# Schematic.net
KiCad netlist of a schematic drawn in EAGLE
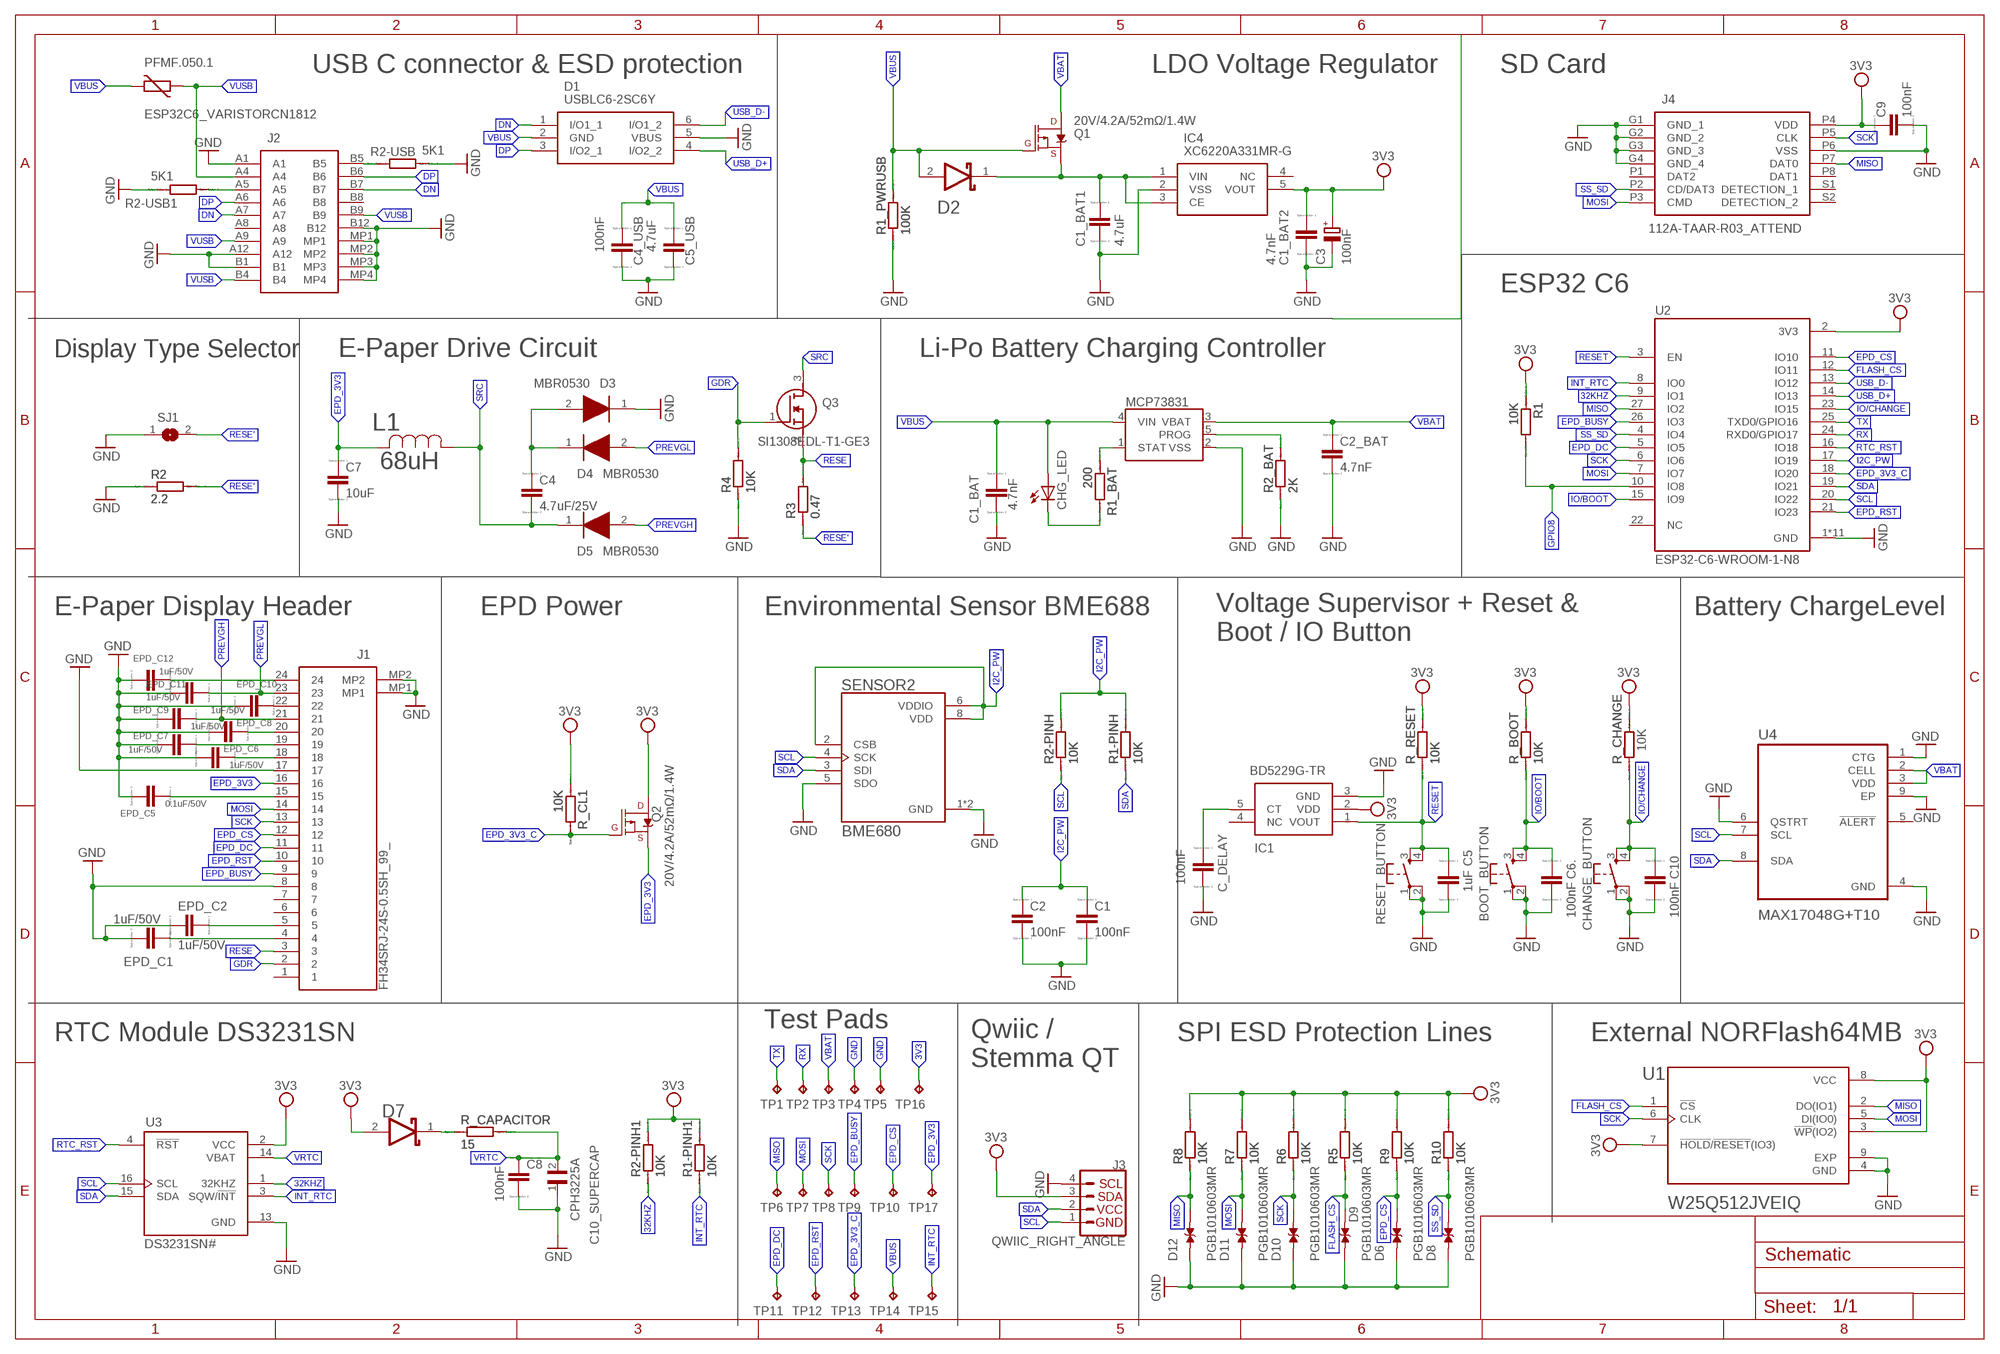
[diagram p0: schematic, sheet 1]

(export (version "E")
  (design (tool "Eeschema 10.0.6"))
  (components
    (comp (ref "BOOT_BUTTON")
      (value "BUTTON_CUSYOMV1")
      (footprint "eagle-import:MYBUTTON")
      (libsource (lib "eagle-import") (part "BUTTON_CUSYOMV1"))
    )
    (comp (ref "C1")
      (value "100nF")
      (footprint "eagle-import:ESP32_WROVER_EAGLE-LTSPICE_C0402")
      (libsource (lib "eagle-import") (part "EAGLE-LTSPICE_CC0402"))
    )
    (comp (ref "C1_BAT")
      (value "4.7nF")
      (footprint "eagle-import:ESP32_WROVER_EAGLE-LTSPICE_C0402")
      (libsource (lib "eagle-import") (part "EAGLE-LTSPICE_CC0402"))
    )
    (comp (ref "C1_BAT1")
      (value "4.7uF")
      (footprint "eagle-import:ESP32_WROVER_EAGLE-LTSPICE_C0402")
      (libsource (lib "eagle-import") (part "EAGLE-LTSPICE_CC0402"))
    )
    (comp (ref "C1_BAT2")
      (value "4.7nF")
      (footprint "eagle-import:ESP32_WROVER_EAGLE-LTSPICE_C0402")
      (libsource (lib "eagle-import") (part "EAGLE-LTSPICE_CC0402"))
    )
    (comp (ref "C2")
      (value "100nF")
      (footprint "eagle-import:ESP32_WROVER_EAGLE-LTSPICE_C0402")
      (libsource (lib "eagle-import") (part "EAGLE-LTSPICE_CC0402"))
    )
    (comp (ref "C2_BAT")
      (value "4.7nF")
      (footprint "eagle-import:ESP32_WROVER_EAGLE-LTSPICE_C0402")
      (libsource (lib "eagle-import") (part "EAGLE-LTSPICE_CC0402"))
    )
    (comp (ref "C3")
      (value "100nF")
      (footprint "eagle-import:RCL_CT3528")
      (libsource (lib "eagle-import") (part "RCL_CPOL-EUCT3528"))
    )
    (comp (ref "C4")
      (value "4.7uF/25V")
      (footprint "eagle-import:ESP32_WROVER_EAGLE-LTSPICE_C0402")
      (libsource (lib "eagle-import") (part "EAGLE-LTSPICE_CC0402"))
    )
    (comp (ref "C4_USB")
      (value "100nF")
      (footprint "eagle-import:ESP32_WROVER_EAGLE-LTSPICE_C0402")
      (libsource (lib "eagle-import") (part "EAGLE-LTSPICE_CC0402"))
    )
    (comp (ref "C5")
      (value "1uF")
      (footprint "eagle-import:ESP32_WROVER_EAGLE-LTSPICE_C0402")
      (libsource (lib "eagle-import") (part "EAGLE-LTSPICE_CC0402"))
    )
    (comp (ref "C5_USB")
      (value "4.7uF")
      (footprint "eagle-import:ESP32_WROVER_EAGLE-LTSPICE_C0402")
      (libsource (lib "eagle-import") (part "EAGLE-LTSPICE_CC0402"))
    )
    (comp (ref "C6.")
      (value "100nF")
      (footprint "eagle-import:ESP32_WROVER_EAGLE-LTSPICE_C0402")
      (libsource (lib "eagle-import") (part "EAGLE-LTSPICE_CC0402"))
    )
    (comp (ref "C7")
      (value "10uF")
      (footprint "eagle-import:ESP32_WROVER_EAGLE-LTSPICE_C0402")
      (libsource (lib "eagle-import") (part "EAGLE-LTSPICE_CC0402"))
    )
    (comp (ref "C8")
      (value "100nF")
      (footprint "eagle-import:ESP32_WROVER_EAGLE-LTSPICE_C0402")
      (libsource (lib "eagle-import") (part "EAGLE-LTSPICE_CC0402"))
    )
    (comp (ref "C9")
      (value "100nF")
      (footprint "eagle-import:ESP32_WROVER_EAGLE-LTSPICE_C0402")
      (libsource (lib "eagle-import") (part "EAGLE-LTSPICE_CC0402"))
    )
    (comp (ref "C10")
      (value "100nF")
      (footprint "eagle-import:ESP32_WROVER_EAGLE-LTSPICE_C0402")
      (libsource (lib "eagle-import") (part "EAGLE-LTSPICE_CC0402"))
    )
    (comp (ref "C10_SUPERCAP")
      (value "CPH3225A")
      (footprint "eagle-import:CAPCP3225X100N")
      (fields (field (name "MF") "Seiko Instruments"))
      (libsource (lib "eagle-import") (part "CPH3225A"))
    )
    (comp (ref "CHANGE_BUTTON")
      (value "BUTTON_CUSYOMV1")
      (footprint "eagle-import:MYBUTTON")
      (libsource (lib "eagle-import") (part "BUTTON_CUSYOMV1"))
    )
    (comp (ref "CHG_LED")
      (value "ADAFRUIT_LEDCHIP-LED0603")
      (footprint "eagle-import:ADAFRUIT_CHIP-LED0603")
      (libsource (lib "eagle-import") (part "ADAFRUIT_LEDCHIP-LED0603"))
    )
    (comp (ref "C_DELAY")
      (value "100nF")
      (footprint "eagle-import:ESP32_WROVER_EAGLE-LTSPICE_C0402")
      (libsource (lib "eagle-import") (part "EAGLE-LTSPICE_CC0402"))
    )
    (comp (ref "D1")
      (value "USBLC6-2SC6Y")
      (footprint "eagle-import:SOT95P280X145-6N")
      (fields (field (name "MF") "STMicroelectronics"))
      (libsource (lib "eagle-import") (part "USBLC6-2SC6Y"))
    )
    (comp (ref "D2")
      (value "ESP32_WROVER_AVX---SD0805S020S1R0_AVX_SD0805S020S1R0_0_0AVX_SD0805S020S1R0_0_0")
      (footprint "eagle-import:ESP32_WROVER_AVX---SD0805S020S1R0_AVX_SD0805S020S1R0_0")
      (fields
        (field (name "DIGIKEY_PART_NUMBER") "478-7800-1-ND")
        (field (name "MF") "AVX")
        (field (name "MOUSER_PART_NUMBER") "581-SD0805S020S1R0")
      )
      (libsource (lib "eagle-import") (part "ESP32_WROVER_AVX---SD0805S020S1R0_AVX_SD0805S020S1R0_0_0AVX_SD0805S020S1R0_0_0"))
    )
    (comp (ref "D3")
      (value "MBR0530")
      (footprint "eagle-import:SOD3716X135N")
      (fields (field (name "MF") "ON Semiconductor"))
      (libsource (lib "eagle-import") (part "MBR0530"))
    )
    (comp (ref "D4")
      (value "MBR0530")
      (footprint "eagle-import:SOD3716X135N")
      (fields (field (name "MF") "ON Semiconductor"))
      (libsource (lib "eagle-import") (part "MBR0530"))
    )
    (comp (ref "D5")
      (value "MBR0530")
      (footprint "eagle-import:SOD3716X135N")
      (fields (field (name "MF") "ON Semiconductor"))
      (libsource (lib "eagle-import") (part "MBR0530"))
    )
    (comp (ref "D6")
      (value "PGB1010603MR")
      (footprint "eagle-import:DIOC1608X36N")
      (fields (field (name "MF") "Littelfuse Inc."))
      (libsource (lib "eagle-import") (part "PGB1010603MR"))
    )
    (comp (ref "D7")
      (value "SD0805S020S1R0")
      (footprint "eagle-import:ESP32_WROVER_AVX---SD0805S020S1R0_AVX_SD0805S020S1R0_0")
      (fields
        (field (name "DIGIKEY_PART_NUMBER") "478-7800-1-ND")
        (field (name "MF") "AVX")
        (field (name "MOUSER_PART_NUMBER") "581-SD0805S020S1R0")
      )
      (libsource (lib "eagle-import") (part "ESP32_WROVER_AVX---SD0805S020S1R0_AVX_SD0805S020S1R0_0_0AVX_SD0805S020S1R0_0_0"))
    )
    (comp (ref "D8")
      (value "PGB1010603MR")
      (footprint "eagle-import:DIOC1608X36N")
      (fields (field (name "MF") "Littelfuse Inc."))
      (libsource (lib "eagle-import") (part "PGB1010603MR"))
    )
    (comp (ref "D9")
      (value "PGB1010603MR")
      (footprint "eagle-import:DIOC1608X36N")
      (fields (field (name "MF") "Littelfuse Inc."))
      (libsource (lib "eagle-import") (part "PGB1010603MR"))
    )
    (comp (ref "D10")
      (value "PGB1010603MR")
      (footprint "eagle-import:DIOC1608X36N")
      (fields (field (name "MF") "Littelfuse Inc."))
      (libsource (lib "eagle-import") (part "PGB1010603MR"))
    )
    (comp (ref "D11")
      (value "PGB1010603MR")
      (footprint "eagle-import:DIOC1608X36N")
      (fields (field (name "MF") "Littelfuse Inc."))
      (libsource (lib "eagle-import") (part "PGB1010603MR"))
    )
    (comp (ref "D12")
      (value "PGB1010603MR")
      (footprint "eagle-import:DIOC1608X36N")
      (fields (field (name "MF") "Littelfuse Inc."))
      (libsource (lib "eagle-import") (part "PGB1010603MR"))
    )
    (comp (ref "EPD_C1")
      (value "1uF/50V")
      (footprint "eagle-import:ESP32_WROVER_EAGLE-LTSPICE_C0402")
      (libsource (lib "eagle-import") (part "EAGLE-LTSPICE_CC0402"))
    )
    (comp (ref "EPD_C2")
      (value "1uF/50V")
      (footprint "eagle-import:ESP32_WROVER_EAGLE-LTSPICE_C0402")
      (libsource (lib "eagle-import") (part "EAGLE-LTSPICE_CC0402"))
    )
    (comp (ref "EPD_C5")
      (value "0.1uF/50V")
      (footprint "eagle-import:ESP32_WROVER_EAGLE-LTSPICE_C0402")
      (libsource (lib "eagle-import") (part "EAGLE-LTSPICE_CC0402"))
    )
    (comp (ref "EPD_C6")
      (value "1uF/50V")
      (footprint "eagle-import:ESP32_WROVER_EAGLE-LTSPICE_C0402")
      (libsource (lib "eagle-import") (part "EAGLE-LTSPICE_CC0402"))
    )
    (comp (ref "EPD_C7")
      (value "1uF/50V")
      (footprint "eagle-import:ESP32_WROVER_EAGLE-LTSPICE_C0402")
      (libsource (lib "eagle-import") (part "EAGLE-LTSPICE_CC0402"))
    )
    (comp (ref "EPD_C8")
      (value "1uF/50V")
      (footprint "eagle-import:ESP32_WROVER_EAGLE-LTSPICE_C0402")
      (libsource (lib "eagle-import") (part "EAGLE-LTSPICE_CC0402"))
    )
    (comp (ref "EPD_C9")
      (value "EAGLE-LTSPICE_CC0402")
      (footprint "eagle-import:ESP32_WROVER_EAGLE-LTSPICE_C0402")
      (libsource (lib "eagle-import") (part "EAGLE-LTSPICE_CC0402"))
    )
    (comp (ref "EPD_C10")
      (value "1uF/50V")
      (footprint "eagle-import:ESP32_WROVER_EAGLE-LTSPICE_C0402")
      (libsource (lib "eagle-import") (part "EAGLE-LTSPICE_CC0402"))
    )
    (comp (ref "EPD_C11")
      (value "1uF/50V")
      (footprint "eagle-import:ESP32_WROVER_EAGLE-LTSPICE_C0402")
      (libsource (lib "eagle-import") (part "EAGLE-LTSPICE_CC0402"))
    )
    (comp (ref "EPD_C12")
      (value "1uF/50V")
      (footprint "eagle-import:ESP32_WROVER_EAGLE-LTSPICE_C0402")
      (libsource (lib "eagle-import") (part "EAGLE-LTSPICE_CC0402"))
    )
    (comp (ref "IC1")
      (value "BD5229G-TR")
      (footprint "eagle-import:SOT95P280X125-5N")
      (fields (field (name "MOUSER_PART_NUMBER") "755-BD5229G-TR"))
      (libsource (lib "eagle-import") (part "BD5229G-TR"))
    )
    (comp (ref "IC4")
      (value "XC6220A331MR-G")
      (footprint "eagle-import:SOT95P280X120-5N")
      (fields (field (name "MOUSER_PART_NUMBER") "865-XC6220A331MR-G"))
      (libsource (lib "eagle-import") (part "XC6220A331MR-G"))
    )
    (comp (ref "J1")
      (value "FH34SRJ-24S-0.5SH_99_")
      (footprint "eagle-import:FH34SRJ24S05SH99")
      (fields
        (field (name "MANUFACTURER_PART_NUMBER") "FH34SRJ-24S-0.5SH(99)")
        (field (name "MOUSER_PART_NUMBER") "798-FH34SRJ24S05SH99")
      )
      (libsource (lib "eagle-import") (part "FH34SRJ-24S-0.5SH_99_"))
    )
    (comp (ref "J2")
      (value "SAMACSYS_PARTS_USB4110-GF-A")
      (footprint "eagle-import:SAMACSYS_PARTS_USB4110GFA")
      (fields
        (field (name "MANUFACTURER_PART_NUMBER") "USB4110-GF-A")
        (field (name "MOUSER_PART_NUMBER") "640-USB4110-GF-A")
      )
      (libsource (lib "eagle-import") (part "SAMACSYS_PARTS_USB4110-GF-A"))
    )
    (comp (ref "J3")
      (value "QWIIC_RIGHT_ANGLE")
      (footprint "eagle-import:JST04_1MM_RA")
      (libsource (lib "eagle-import") (part "QWIIC_CONNECTORJS-1MM"))
    )
    (comp (ref "J4")
      (value "112A-TAAR-R03_ATTEND")
      (footprint "eagle-import:112ATAARR03ATTEND")
      (fields (field (name "MANUFACTURER_PART_NUMBER") "112A-TAAR-R03 ATTEND"))
      (libsource (lib "eagle-import") (part "112A-TAAR-R03_ATTEND"))
    )
    (comp (ref "L1")
      (value "68uH")
      (footprint "eagle-import:IND_4828-WE-TPC_WRE")
      (fields
        (field (name "MANUFACTURER_PART_NUMBER") "744043680")
        (field (name "COPYRIGHT") "Copyright (C) 2024 Ultra Librarian. All rights reserved.")
      )
      (libsource (lib "eagle-import") (part "744043680IND_4828-WE-TPC_WRE"))
    )
    (comp (ref "MCP73831")
      (value "MCP73831")
      (footprint "eagle-import:ESP32_WROVER_SPARKFUN-IC-POWER_SOT23-5")
      (libsource (lib "eagle-import") (part "ESP32_WROVER_SPARKFUN-IC-POWER_MCP73831"))
    )
    (comp (ref "PFMF.050.1")
      (value "ESP32C6_VARISTORCN1812")
      (footprint "eagle-import:ESP32C6_VARISTOR_CT_CN1812")
      (libsource (lib "eagle-import") (part "ESP32C6_VARISTORCN1812"))
    )
    (comp (ref "Q1")
      (value "20V/4.2A/52mΩ/1.4W")
      (footprint "eagle-import:ESP32_WROVER_SPARKFUN-DISCRETESEMI_SOT23-3")
      (libsource (lib "eagle-import") (part "ESP32_WROVER_SPARKFUN-DISCRETESEMI_MOSFET_PCH-DMG2305UX-7"))
    )
    (comp (ref "Q2")
      (value "20V/4.2A/52mΩ/1.4W")
      (footprint "eagle-import:ESP32_WROVER_SPARKFUN-DISCRETESEMI_SOT23-3")
      (libsource (lib "eagle-import") (part "ESP32_WROVER_SPARKFUN-DISCRETESEMI_MOSFET_PCH-DMG2305UX-7"))
    )
    (comp (ref "Q3")
      (value "SI1308EDL-T1-GE3")
      (footprint "eagle-import:SOT65P210X110-3N")
      (fields (field (name "MF") "Vishay Siliconix"))
      (libsource (lib "eagle-import") (part "SI1308EDL-T1-GE3"))
    )
    (comp (ref "R1")
      (value "10K")
      (footprint "eagle-import:ESP32_WROVER_EAGLE-LTSPICE_R0402")
      (libsource (lib "eagle-import") (part "ESP32_WROVER_EAGLE-LTSPICE_RR0402"))
    )
    (comp (ref "R1-PINH")
      (value "10K")
      (footprint "eagle-import:ESP32_WROVER_EAGLE-LTSPICE_R0402")
      (libsource (lib "eagle-import") (part "ESP32_WROVER_EAGLE-LTSPICE_RR0402"))
    )
    (comp (ref "R1-PINH1")
      (value "10K")
      (footprint "eagle-import:ESP32_WROVER_EAGLE-LTSPICE_R0402")
      (libsource (lib "eagle-import") (part "ESP32_WROVER_EAGLE-LTSPICE_RR0402"))
    )
    (comp (ref "R1_BAT")
      (value "200")
      (footprint "eagle-import:ESP32_WROVER_EAGLE-LTSPICE_R0402")
      (libsource (lib "eagle-import") (part "ESP32_WROVER_EAGLE-LTSPICE_RR0402"))
    )
    (comp (ref "R1_PWRUSB")
      (value "100K")
      (footprint "eagle-import:ESP32_WROVER_EAGLE-LTSPICE_R0402")
      (libsource (lib "eagle-import") (part "ESP32_WROVER_EAGLE-LTSPICE_RR0402"))
    )
    (comp (ref "R2")
      (value "2.2")
      (footprint "eagle-import:ESP32_WROVER_EAGLE-LTSPICE_R0402")
      (libsource (lib "eagle-import") (part "ESP32_WROVER_EAGLE-LTSPICE_RR0402"))
    )
    (comp (ref "R2-PINH")
      (value "10K")
      (footprint "eagle-import:ESP32_WROVER_EAGLE-LTSPICE_R0402")
      (libsource (lib "eagle-import") (part "ESP32_WROVER_EAGLE-LTSPICE_RR0402"))
    )
    (comp (ref "R2-PINH1")
      (value "10K")
      (footprint "eagle-import:ESP32_WROVER_EAGLE-LTSPICE_R0402")
      (libsource (lib "eagle-import") (part "ESP32_WROVER_EAGLE-LTSPICE_RR0402"))
    )
    (comp (ref "R2-USB")
      (value "5K1")
      (footprint "eagle-import:ESP32_WROVER_EAGLE-LTSPICE_R0402")
      (libsource (lib "eagle-import") (part "ESP32_WROVER_EAGLE-LTSPICE_RR0402"))
    )
    (comp (ref "R2-USB1")
      (value "5K1")
      (footprint "eagle-import:ESP32_WROVER_EAGLE-LTSPICE_R0402")
      (libsource (lib "eagle-import") (part "ESP32_WROVER_EAGLE-LTSPICE_RR0402"))
    )
    (comp (ref "R2_BAT")
      (value "2K")
      (footprint "eagle-import:ESP32_WROVER_EAGLE-LTSPICE_R0402")
      (libsource (lib "eagle-import") (part "ESP32_WROVER_EAGLE-LTSPICE_RR0402"))
    )
    (comp (ref "R3")
      (value "0.47")
      (footprint "eagle-import:ESP32_WROVER_EAGLE-LTSPICE_R0402")
      (libsource (lib "eagle-import") (part "ESP32_WROVER_EAGLE-LTSPICE_RR0402"))
    )
    (comp (ref "R4")
      (value "10K")
      (footprint "eagle-import:ESP32_WROVER_EAGLE-LTSPICE_R0402")
      (libsource (lib "eagle-import") (part "ESP32_WROVER_EAGLE-LTSPICE_RR0402"))
    )
    (comp (ref "R5")
      (value "10K")
      (footprint "eagle-import:ESP32_WROVER_EAGLE-LTSPICE_R0402")
      (libsource (lib "eagle-import") (part "ESP32_WROVER_EAGLE-LTSPICE_RR0402"))
    )
    (comp (ref "R6")
      (value "10K")
      (footprint "eagle-import:ESP32_WROVER_EAGLE-LTSPICE_R0402")
      (libsource (lib "eagle-import") (part "ESP32_WROVER_EAGLE-LTSPICE_RR0402"))
    )
    (comp (ref "R7")
      (value "10K")
      (footprint "eagle-import:ESP32_WROVER_EAGLE-LTSPICE_R0402")
      (libsource (lib "eagle-import") (part "ESP32_WROVER_EAGLE-LTSPICE_RR0402"))
    )
    (comp (ref "R8")
      (value "10K")
      (footprint "eagle-import:ESP32_WROVER_EAGLE-LTSPICE_R0402")
      (libsource (lib "eagle-import") (part "ESP32_WROVER_EAGLE-LTSPICE_RR0402"))
    )
    (comp (ref "R9")
      (value "10K")
      (footprint "eagle-import:ESP32_WROVER_EAGLE-LTSPICE_R0402")
      (libsource (lib "eagle-import") (part "ESP32_WROVER_EAGLE-LTSPICE_RR0402"))
    )
    (comp (ref "R10")
      (value "10K")
      (footprint "eagle-import:ESP32_WROVER_EAGLE-LTSPICE_R0402")
      (libsource (lib "eagle-import") (part "ESP32_WROVER_EAGLE-LTSPICE_RR0402"))
    )
    (comp (ref "RESET_BUTTON")
      (value "BUTTON_CUSYOMV1")
      (footprint "eagle-import:MYBUTTON")
      (libsource (lib "eagle-import") (part "BUTTON_CUSYOMV1"))
    )
    (comp (ref "R_BOOT")
      (value "10K")
      (footprint "eagle-import:ESP32_WROVER_EAGLE-LTSPICE_R0402")
      (libsource (lib "eagle-import") (part "ESP32_WROVER_EAGLE-LTSPICE_RR0402"))
    )
    (comp (ref "R_CAPACITOR")
      (value "15")
      (footprint "eagle-import:ESP32_WROVER_EAGLE-LTSPICE_R0402")
      (libsource (lib "eagle-import") (part "ESP32_WROVER_EAGLE-LTSPICE_RR0402"))
    )
    (comp (ref "R_CHANGE")
      (value "10K")
      (footprint "eagle-import:ESP32_WROVER_EAGLE-LTSPICE_R0402")
      (libsource (lib "eagle-import") (part "ESP32_WROVER_EAGLE-LTSPICE_RR0402"))
    )
    (comp (ref "R_CL1")
      (value "10K")
      (footprint "eagle-import:ESP32_WROVER_EAGLE-LTSPICE_R0402")
      (libsource (lib "eagle-import") (part "ESP32_WROVER_EAGLE-LTSPICE_RR0402"))
    )
    (comp (ref "R_RESET")
      (value "10K")
      (footprint "eagle-import:ESP32_WROVER_EAGLE-LTSPICE_R0402")
      (libsource (lib "eagle-import") (part "ESP32_WROVER_EAGLE-LTSPICE_RR0402"))
    )
    (comp (ref "SENSOR2")
      (value "BME680")
      (footprint "eagle-import:ESP32_WROVER_BME680_PSON80P300X300X100-8N")
      (fields (field (name "MF") "Bosch Sensortec"))
      (libsource (lib "eagle-import") (part "ESP32_WROVER_BME680_BME680"))
    )
    (comp (ref "SJ1") (value "SJ") (footprint "eagle-import:SJ") (libsource (lib "eagle-import") (part "SJ")))
    (comp (ref "TP1")
      (value "TPTP20R")
      (footprint "eagle-import:TP20R")
      (libsource (lib "eagle-import") (part "TPTP20R"))
    )
    (comp (ref "TP2")
      (value "TPTP20R")
      (footprint "eagle-import:TP20R")
      (libsource (lib "eagle-import") (part "TPTP20R"))
    )
    (comp (ref "TP3")
      (value "TPTP20R")
      (footprint "eagle-import:TP20R")
      (libsource (lib "eagle-import") (part "TPTP20R"))
    )
    (comp (ref "TP4")
      (value "TPTP20R")
      (footprint "eagle-import:TP20R")
      (libsource (lib "eagle-import") (part "TPTP20R"))
    )
    (comp (ref "TP5")
      (value "TPTP20R")
      (footprint "eagle-import:TP20R")
      (libsource (lib "eagle-import") (part "TPTP20R"))
    )
    (comp (ref "TP6")
      (value "TPTP20R")
      (footprint "eagle-import:TP20R")
      (libsource (lib "eagle-import") (part "TPTP20R"))
    )
    (comp (ref "TP7")
      (value "TPTP20R")
      (footprint "eagle-import:TP20R")
      (libsource (lib "eagle-import") (part "TPTP20R"))
    )
    (comp (ref "TP8")
      (value "TPTP20R")
      (footprint "eagle-import:TP20R")
      (libsource (lib "eagle-import") (part "TPTP20R"))
    )
    (comp (ref "TP9")
      (value "TPTP20R")
      (footprint "eagle-import:TP20R")
      (libsource (lib "eagle-import") (part "TPTP20R"))
    )
    (comp (ref "TP10")
      (value "TPTP20R")
      (footprint "eagle-import:TP20R")
      (libsource (lib "eagle-import") (part "TPTP20R"))
    )
    (comp (ref "TP11")
      (value "TPTP20R")
      (footprint "eagle-import:TP20R")
      (libsource (lib "eagle-import") (part "TPTP20R"))
    )
    (comp (ref "TP12")
      (value "TPTP20R")
      (footprint "eagle-import:TP20R")
      (libsource (lib "eagle-import") (part "TPTP20R"))
    )
    (comp (ref "TP13")
      (value "TPTP20R")
      (footprint "eagle-import:TP20R")
      (libsource (lib "eagle-import") (part "TPTP20R"))
    )
    (comp (ref "TP14")
      (value "TPTP20R")
      (footprint "eagle-import:TP20R")
      (libsource (lib "eagle-import") (part "TPTP20R"))
    )
    (comp (ref "TP15")
      (value "TPTP20R")
      (footprint "eagle-import:TP20R")
      (libsource (lib "eagle-import") (part "TPTP20R"))
    )
    (comp (ref "TP16")
      (value "TPTP20R")
      (footprint "eagle-import:TP20R")
      (libsource (lib "eagle-import") (part "TPTP20R"))
    )
    (comp (ref "TP17")
      (value "TPTP20R")
      (footprint "eagle-import:TP20R")
      (libsource (lib "eagle-import") (part "TPTP20R"))
    )
    (comp (ref "U1")
      (value "W25Q512JVEIQ")
      (footprint "eagle-import:SON127P600X800X80-9N")
      (fields (field (name "MF") "Winbond Electronics"))
      (libsource (lib "eagle-import") (part "W25Q512JVEIQ"))
    )
    (comp (ref "U2")
      (value "ESP32-C6-WROOM-1-N8")
      (footprint "eagle-import:XCVR_ESP32-C6-WROOM-1-N8")
      (fields (field (name "MF") "Espressif Systems"))
      (libsource (lib "eagle-import") (part "ESP32-C6-WROOM-1-N8"))
    )
    (comp (ref "U3")
      (value "DS3231SN#")
      (footprint "eagle-import:SOIC127P1032X265-16N")
      (fields (field (name "MF") "Analog Devices"))
      (libsource (lib "eagle-import") (part "DS3231SN#"))
    )
    (comp (ref "U4")
      (value "MAX17048G+T10")
      (footprint "eagle-import:SON50P200X200X80-9N")
      (fields (field (name "MF") "Analog Devices"))
      (libsource (lib "eagle-import") (part "MAX17048G+T10"))
    )
  )
  (nets
    (net (code "1") (name "3V3") (class "Default")
      (node (ref "C1_BAT2") (pin "1") (pinfunction "1_1") (pintype "passive"))
      (node (ref "C3") (pin "+") (pinfunction "+_+") (pintype "passive"))
      (node (ref "C9") (pin "1") (pinfunction "1_1") (pintype "passive"))
      (node (ref "D7") (pin "2") (pinfunction "ANODE_2") (pintype "bidirectional"))
      (node (ref "IC1") (pin "2") (pinfunction "VDD_2") (pintype "bidirectional"))
      (node (ref "IC4") (pin "5") (pinfunction "VOUT_5") (pintype "bidirectional"))
      (node (ref "J3") (pin "3") (pinfunction "3_3") (pintype "passive"))
      (node (ref "J4") (pin "P4") (pinfunction "VDD_P4") (pintype "bidirectional"))
      (node (ref "Q2") (pin "3") (pinfunction "D_3") (pintype "bidirectional"))
      (node (ref "R1") (pin "1") (pinfunction "1_1") (pintype "passive"))
      (node (ref "R1-PINH1") (pin "2") (pinfunction "2_2") (pintype "passive"))
      (node (ref "R10") (pin "2") (pinfunction "2_2") (pintype "passive"))
      (node (ref "R2-PINH1") (pin "2") (pinfunction "2_2") (pintype "passive"))
      (node (ref "R5") (pin "2") (pinfunction "2_2") (pintype "passive"))
      (node (ref "R6") (pin "2") (pinfunction "2_2") (pintype "passive"))
      (node (ref "R7") (pin "2") (pinfunction "2_2") (pintype "passive"))
      (node (ref "R8") (pin "2") (pinfunction "2_2") (pintype "passive"))
      (node (ref "R9") (pin "2") (pinfunction "2_2") (pintype "passive"))
      (node (ref "R_BOOT") (pin "2") (pinfunction "2_2") (pintype "passive"))
      (node (ref "R_CHANGE") (pin "2") (pinfunction "2_2") (pintype "passive"))
      (node (ref "R_CL1") (pin "1") (pinfunction "1_1") (pintype "passive"))
      (node (ref "R_RESET") (pin "2") (pinfunction "2_2") (pintype "passive"))
      (node (ref "TP16") (pin "TP") (pinfunction "TP_TP") (pintype "input"))
      (node (ref "U1") (pin "3") (pinfunction "~{WP}(IO2)_3") (pintype "bidirectional"))
      (node (ref "U1") (pin "7") (pinfunction "~{HOLD}/~{RESET}(IO3)_7") (pintype "bidirectional"))
      (node (ref "U1") (pin "8") (pinfunction "VCC_8") (pintype "power_in"))
      (node (ref "U2") (pin "2") (pinfunction "3V3_2") (pintype "power_in"))
      (node (ref "U3") (pin "2") (pinfunction "VCC_2") (pintype "power_in"))
    )
    (net (code "2") (name "32KHZ") (class "Default")
      (node (ref "R2-PINH1") (pin "1") (pinfunction "1_1") (pintype "passive"))
      (node (ref "U2") (pin "9") (pinfunction "IO1_9") (pintype "bidirectional"))
      (node (ref "U3") (pin "1") (pinfunction "32KHZ_1") (pintype "output"))
    )
    (net (code "3") (name "DN") (class "Default")
      (node (ref "D1") (pin "1") (pinfunction "I/O1_1_1") (pintype "bidirectional"))
      (node (ref "J2") (pin "A7") (pinfunction "A7_A7") (pintype "bidirectional"))
      (node (ref "J2") (pin "B7") (pinfunction "B7_B7") (pintype "bidirectional"))
    )
    (net (code "4") (name "DP") (class "Default")
      (node (ref "D1") (pin "3") (pinfunction "I/O2_1_3") (pintype "bidirectional"))
      (node (ref "J2") (pin "A6") (pinfunction "A6_A6") (pintype "bidirectional"))
      (node (ref "J2") (pin "B6") (pinfunction "B6_B6") (pintype "bidirectional"))
    )
    (net (code "5") (name "EPD_3V3") (class "Default")
      (node (ref "C7") (pin "1") (pinfunction "1_1") (pintype "passive"))
      (node (ref "J1") (pin "16") (pinfunction "16_16") (pintype "bidirectional"))
      (node (ref "L1") (pin "2") (pinfunction "2_2") (pintype "passive"))
      (node (ref "Q2") (pin "2") (pinfunction "S_2") (pintype "bidirectional"))
      (node (ref "TP17") (pin "TP") (pinfunction "TP_TP") (pintype "input"))
    )
    (net (code "6") (name "EPD_3V3_C") (class "Default")
      (node (ref "Q2") (pin "1") (pinfunction "G_1") (pintype "bidirectional"))
      (node (ref "R_CL1") (pin "2") (pinfunction "2_2") (pintype "passive"))
      (node (ref "TP13") (pin "TP") (pinfunction "TP_TP") (pintype "input"))
      (node (ref "U2") (pin "18") (pinfunction "IO20_18") (pintype "bidirectional"))
    )
    (net (code "7") (name "EPD_BUSY") (class "Default")
      (node (ref "J1") (pin "9") (pinfunction "9_9") (pintype "bidirectional"))
      (node (ref "TP9") (pin "TP") (pinfunction "TP_TP") (pintype "input"))
      (node (ref "U2") (pin "26") (pinfunction "IO3_26") (pintype "bidirectional"))
    )
    (net (code "8") (name "EPD_CS") (class "Default")
      (node (ref "D6") (pin "2") (pinfunction "2_2") (pintype "passive"))
      (node (ref "J1") (pin "12") (pinfunction "12_12") (pintype "bidirectional"))
      (node (ref "R9") (pin "1") (pinfunction "1_1") (pintype "passive"))
      (node (ref "TP10") (pin "TP") (pinfunction "TP_TP") (pintype "input"))
      (node (ref "U2") (pin "11") (pinfunction "IO10_11") (pintype "bidirectional"))
    )
    (net (code "9") (name "EPD_DC") (class "Default")
      (node (ref "J1") (pin "11") (pinfunction "11_11") (pintype "bidirectional"))
      (node (ref "TP11") (pin "TP") (pinfunction "TP_TP") (pintype "input"))
      (node (ref "U2") (pin "5") (pinfunction "IO5_5") (pintype "bidirectional"))
    )
    (net (code "10") (name "EPD_RST") (class "Default")
      (node (ref "J1") (pin "10") (pinfunction "10_10") (pintype "bidirectional"))
      (node (ref "TP12") (pin "TP") (pinfunction "TP_TP") (pintype "input"))
      (node (ref "U2") (pin "21") (pinfunction "IO23_21") (pintype "bidirectional"))
    )
    (net (code "11") (name "FLASH_CS") (class "Default")
      (node (ref "D9") (pin "2") (pinfunction "2_2") (pintype "passive"))
      (node (ref "R5") (pin "1") (pinfunction "1_1") (pintype "passive"))
      (node (ref "U1") (pin "1") (pinfunction "~{CS}_1") (pintype "input"))
      (node (ref "U2") (pin "12") (pinfunction "IO11_12") (pintype "bidirectional"))
    )
    (net (code "12") (name "GDR") (class "Default")
      (node (ref "J1") (pin "2") (pinfunction "2_2") (pintype "bidirectional"))
      (node (ref "Q3") (pin "1") (pinfunction "G_1") (pintype "bidirectional"))
      (node (ref "R4") (pin "2") (pinfunction "2_2") (pintype "passive"))
    )
    (net (code "13") (name "GND") (class "Default")
      (node (ref "BOOT_BUTTON") (pin "1") (pinfunction "1_1") (pintype "passive"))
      (node (ref "BOOT_BUTTON") (pin "2") (pinfunction "2_2") (pintype "passive"))
      (node (ref "C1") (pin "2") (pinfunction "2_2") (pintype "passive"))
      (node (ref "C10") (pin "2") (pinfunction "2_2") (pintype "passive"))
      (node (ref "C10_SUPERCAP") (pin "1") (pinfunction "1_1") (pintype "passive"))
      (node (ref "C1_BAT") (pin "2") (pinfunction "2_2") (pintype "passive"))
      (node (ref "C1_BAT1") (pin "2") (pinfunction "2_2") (pintype "passive"))
      (node (ref "C1_BAT2") (pin "2") (pinfunction "2_2") (pintype "passive"))
      (node (ref "C2") (pin "2") (pinfunction "2_2") (pintype "passive"))
      (node (ref "C2_BAT") (pin "2") (pinfunction "2_2") (pintype "passive"))
      (node (ref "C3") (pin "-") (pinfunction "-_-") (pintype "passive"))
      (node (ref "C4_USB") (pin "2") (pinfunction "2_2") (pintype "passive"))
      (node (ref "C5") (pin "2") (pinfunction "2_2") (pintype "passive"))
      (node (ref "C5_USB") (pin "2") (pinfunction "2_2") (pintype "passive"))
      (node (ref "C6.") (pin "2") (pinfunction "2_2") (pintype "passive"))
      (node (ref "C7") (pin "2") (pinfunction "2_2") (pintype "passive"))
      (node (ref "C8") (pin "2") (pinfunction "2_2") (pintype "passive"))
      (node (ref "C9") (pin "2") (pinfunction "2_2") (pintype "passive"))
      (node (ref "CHANGE_BUTTON") (pin "1") (pinfunction "1_1") (pintype "passive"))
      (node (ref "CHANGE_BUTTON") (pin "2") (pinfunction "2_2") (pintype "passive"))
      (node (ref "C_DELAY") (pin "2") (pinfunction "2_2") (pintype "passive"))
      (node (ref "D1") (pin "5") (pinfunction "VBUS_5") (pintype "bidirectional"))
      (node (ref "D10") (pin "1") (pinfunction "1_1") (pintype "passive"))
      (node (ref "D11") (pin "1") (pinfunction "1_1") (pintype "passive"))
      (node (ref "D12") (pin "1") (pinfunction "1_1") (pintype "passive"))
      (node (ref "D3") (pin "1") (pinfunction "K_1") (pintype "bidirectional"))
      (node (ref "D6") (pin "1") (pinfunction "1_1") (pintype "passive"))
      (node (ref "D8") (pin "1") (pinfunction "1_1") (pintype "passive"))
      (node (ref "D9") (pin "1") (pinfunction "1_1") (pintype "passive"))
      (node (ref "EPD_C1") (pin "2") (pinfunction "2_2") (pintype "passive"))
      (node (ref "EPD_C10") (pin "2") (pinfunction "2_2") (pintype "passive"))
      (node (ref "EPD_C11") (pin "2") (pinfunction "2_2") (pintype "passive"))
      (node (ref "EPD_C12") (pin "2") (pinfunction "2_2") (pintype "passive"))
      (node (ref "EPD_C2") (pin "2") (pinfunction "2_2") (pintype "passive"))
      (node (ref "EPD_C5") (pin "2") (pinfunction "2_2") (pintype "passive"))
      (node (ref "EPD_C6") (pin "2") (pinfunction "2_2") (pintype "passive"))
      (node (ref "EPD_C7") (pin "2") (pinfunction "2_2") (pintype "passive"))
      (node (ref "EPD_C8") (pin "2") (pinfunction "2_2") (pintype "passive"))
      (node (ref "EPD_C9") (pin "2") (pinfunction "2_2") (pintype "passive"))
      (node (ref "IC1") (pin "3") (pinfunction "GND_3") (pintype "bidirectional"))
      (node (ref "IC4") (pin "2") (pinfunction "VSS_2") (pintype "bidirectional"))
      (node (ref "J1") (pin "17") (pinfunction "17_17") (pintype "bidirectional"))
      (node (ref "J1") (pin "8") (pinfunction "8_8") (pintype "bidirectional"))
      (node (ref "J1") (pin "MP1") (pinfunction "MP1_MP1") (pintype "bidirectional"))
      (node (ref "J1") (pin "MP2") (pinfunction "MP2_MP2") (pintype "bidirectional"))
      (node (ref "J2") (pin "A1") (pinfunction "A1_A1") (pintype "bidirectional"))
      (node (ref "J2") (pin "A12") (pinfunction "A12_A12") (pintype "bidirectional"))
      (node (ref "J2") (pin "B1") (pinfunction "B1_B1") (pintype "bidirectional"))
      (node (ref "J2") (pin "B12") (pinfunction "B12_B12") (pintype "bidirectional"))
      (node (ref "J2") (pin "MP1") (pinfunction "MP1_MP1") (pintype "bidirectional"))
      (node (ref "J2") (pin "MP2") (pinfunction "MP2_MP2") (pintype "bidirectional"))
      (node (ref "J2") (pin "MP3") (pinfunction "MP3_MP3") (pintype "bidirectional"))
      (node (ref "J2") (pin "MP4") (pinfunction "MP4_MP4") (pintype "bidirectional"))
      (node (ref "J3") (pin "4") (pinfunction "4_4") (pintype "passive"))
      (node (ref "J4") (pin "G1") (pinfunction "GND_1_G1") (pintype "bidirectional"))
      (node (ref "J4") (pin "G2") (pinfunction "GND_2_G2") (pintype "bidirectional"))
      (node (ref "J4") (pin "G3") (pinfunction "GND_3_G3") (pintype "bidirectional"))
      (node (ref "J4") (pin "G4") (pinfunction "GND_4_G4") (pintype "bidirectional"))
      (node (ref "J4") (pin "P6") (pinfunction "VSS_P6") (pintype "bidirectional"))
      (node (ref "MCP73831") (pin "2") (pinfunction "VSS_2") (pintype "power_in"))
      (node (ref "R1_PWRUSB") (pin "1") (pinfunction "1_1") (pintype "passive"))
      (node (ref "R2") (pin "1") (pinfunction "1_1") (pintype "passive"))
      (node (ref "R2-USB") (pin "2") (pinfunction "2_2") (pintype "passive"))
      (node (ref "R2-USB1") (pin "1") (pinfunction "1_1") (pintype "passive"))
      (node (ref "R2_BAT") (pin "1") (pinfunction "1_1") (pintype "passive"))
      (node (ref "R4") (pin "1") (pinfunction "1_1") (pintype "passive"))
      (node (ref "RESET_BUTTON") (pin "1") (pinfunction "1_1") (pintype "passive"))
      (node (ref "RESET_BUTTON") (pin "2") (pinfunction "2_2") (pintype "passive"))
      (node (ref "SENSOR2") (pin "1") (pinfunction "GND_1") (pintype "power_in"))
      (node (ref "SENSOR2") (pin "5") (pinfunction "SDO_5") (pintype "bidirectional"))
      (node (ref "SENSOR2") (pin "7") (pinfunction "GND_7") (pintype "power_in"))
      (node (ref "SJ1") (pin "1") (pinfunction "1_1") (pintype "passive"))
      (node (ref "TP4") (pin "TP") (pinfunction "TP_TP") (pintype "input"))
      (node (ref "TP5") (pin "TP") (pinfunction "TP_TP") (pintype "input"))
      (node (ref "U1") (pin "4") (pinfunction "GND_4") (pintype "power_in"))
      (node (ref "U1") (pin "9") (pinfunction "EXP_9") (pintype "passive"))
      (node (ref "U2") (pin "1") (pinfunction "GND_1") (pintype "power_in"))
      (node (ref "U2") (pin "28") (pinfunction "GND_28") (pintype "power_in"))
      (node (ref "U2") (pin "29_1") (pinfunction "GND_29_1") (pintype "power_in"))
      (node (ref "U2") (pin "29_2") (pinfunction "GND_29_2") (pintype "power_in"))
      (node (ref "U2") (pin "29_3") (pinfunction "GND_29_3") (pintype "power_in"))
      (node (ref "U2") (pin "29_4") (pinfunction "GND_29_4") (pintype "power_in"))
      (node (ref "U2") (pin "29_5") (pinfunction "GND_29_5") (pintype "power_in"))
      (node (ref "U2") (pin "29_6") (pinfunction "GND_29_6") (pintype "power_in"))
      (node (ref "U2") (pin "29_7") (pinfunction "GND_29_7") (pintype "power_in"))
      (node (ref "U2") (pin "29_8") (pinfunction "GND_29_8") (pintype "power_in"))
      (node (ref "U2") (pin "29_9") (pinfunction "GND_29_9") (pintype "power_in"))
      (node (ref "U3") (pin "13") (pinfunction "GND_13") (pintype "power_in"))
      (node (ref "U4") (pin "1") (pinfunction "CTG_1") (pintype "power_in"))
      (node (ref "U4") (pin "4") (pinfunction "GND_4") (pintype "power_in"))
      (node (ref "U4") (pin "6") (pinfunction "QSTRT_6") (pintype "input"))
      (node (ref "U4") (pin "9") (pinfunction "EP_9") (pintype "power_in"))
    )
    (net (code "14") (name "GPIO8") (class "Default")
      (node (ref "R1") (pin "2") (pinfunction "2_2") (pintype "passive"))
      (node (ref "U2") (pin "10") (pinfunction "IO8_10") (pintype "bidirectional"))
    )
    (net (code "15") (name "I2C_PW") (class "Default")
      (node (ref "C1") (pin "1") (pinfunction "1_1") (pintype "passive"))
      (node (ref "C2") (pin "1") (pinfunction "1_1") (pintype "passive"))
      (node (ref "R1-PINH") (pin "2") (pinfunction "2_2") (pintype "passive"))
      (node (ref "R2-PINH") (pin "2") (pinfunction "2_2") (pintype "passive"))
      (node (ref "SENSOR2") (pin "2") (pinfunction "CSB_2") (pintype "input"))
      (node (ref "SENSOR2") (pin "6") (pinfunction "VDDIO_6") (pintype "power_in"))
      (node (ref "SENSOR2") (pin "8") (pinfunction "VDD_8") (pintype "power_in"))
      (node (ref "U2") (pin "17") (pinfunction "IO19_17") (pintype "bidirectional"))
    )
    (net (code "16") (name "INT_RTC") (class "Default")
      (node (ref "R1-PINH1") (pin "1") (pinfunction "1_1") (pintype "passive"))
      (node (ref "TP15") (pin "TP") (pinfunction "TP_TP") (pintype "input"))
      (node (ref "U2") (pin "8") (pinfunction "IO0_8") (pintype "bidirectional"))
      (node (ref "U3") (pin "3") (pinfunction "SQW/~{INT}_3") (pintype "output"))
    )
    (net (code "17") (name "IO{slash}BOOT") (class "Default")
      (node (ref "BOOT_BUTTON") (pin "3") (pinfunction "3_3") (pintype "passive"))
      (node (ref "BOOT_BUTTON") (pin "4") (pinfunction "4_4") (pintype "passive"))
      (node (ref "C6.") (pin "1") (pinfunction "1_1") (pintype "passive"))
      (node (ref "R_BOOT") (pin "1") (pinfunction "1_1") (pintype "passive"))
      (node (ref "U2") (pin "15") (pinfunction "IO9_15") (pintype "bidirectional"))
    )
    (net (code "18") (name "IO{slash}CHANGE") (class "Default")
      (node (ref "C10") (pin "1") (pinfunction "1_1") (pintype "passive"))
      (node (ref "CHANGE_BUTTON") (pin "3") (pinfunction "3_3") (pintype "passive"))
      (node (ref "CHANGE_BUTTON") (pin "4") (pinfunction "4_4") (pintype "passive"))
      (node (ref "R_CHANGE") (pin "1") (pinfunction "1_1") (pintype "passive"))
      (node (ref "U2") (pin "23") (pinfunction "IO15_23") (pintype "bidirectional"))
    )
    (net (code "19") (name "MISO") (class "Default")
      (node (ref "D12") (pin "2") (pinfunction "2_2") (pintype "passive"))
      (node (ref "J4") (pin "P7") (pinfunction "DAT0_P7") (pintype "bidirectional"))
      (node (ref "R8") (pin "1") (pinfunction "1_1") (pintype "passive"))
      (node (ref "TP6") (pin "TP") (pinfunction "TP_TP") (pintype "input"))
      (node (ref "U1") (pin "2") (pinfunction "DO(IO1)_2") (pintype "bidirectional"))
      (node (ref "U2") (pin "27") (pinfunction "IO2_27") (pintype "bidirectional"))
    )
    (net (code "20") (name "MOSI") (class "Default")
      (node (ref "D11") (pin "2") (pinfunction "2_2") (pintype "passive"))
      (node (ref "J1") (pin "14") (pinfunction "14_14") (pintype "bidirectional"))
      (node (ref "J4") (pin "P3") (pinfunction "CMD_P3") (pintype "bidirectional"))
      (node (ref "R7") (pin "1") (pinfunction "1_1") (pintype "passive"))
      (node (ref "TP7") (pin "TP") (pinfunction "TP_TP") (pintype "input"))
      (node (ref "U1") (pin "5") (pinfunction "DI(IO0)_5") (pintype "bidirectional"))
      (node (ref "U2") (pin "7") (pinfunction "IO7_7") (pintype "bidirectional"))
    )
    (net (code "21") (name "Net-(CHG_LED-PadC)") (class "Default")
      (node (ref "CHG_LED") (pin "C") (pinfunction "C_C") (pintype "passive"))
      (node (ref "R1_BAT") (pin "2") (pinfunction "2_2") (pintype "passive"))
    )
    (net (code "22") (name "Net-(D2-CATHODE)") (class "Default")
      (node (ref "C1_BAT1") (pin "1") (pinfunction "1_1") (pintype "passive"))
      (node (ref "D2") (pin "1") (pinfunction "CATHODE_1") (pintype "bidirectional"))
      (node (ref "IC4") (pin "1") (pinfunction "VIN_1") (pintype "bidirectional"))
      (node (ref "IC4") (pin "3") (pinfunction "CE_3") (pintype "bidirectional"))
      (node (ref "Q1") (pin "2") (pinfunction "S_2") (pintype "bidirectional"))
    )
    (net (code "23") (name "Net-(D3-A)") (class "Default")
      (node (ref "C4") (pin "1") (pinfunction "1_1") (pintype "passive"))
      (node (ref "D3") (pin "2") (pinfunction "A_2") (pintype "bidirectional"))
      (node (ref "D4") (pin "1") (pinfunction "K_1") (pintype "bidirectional"))
    )
    (net (code "24") (name "Net-(D7-CATHODE)") (class "Default")
      (node (ref "D7") (pin "1") (pinfunction "CATHODE_1") (pintype "bidirectional"))
      (node (ref "R_CAPACITOR") (pin "1") (pinfunction "1_1") (pintype "passive"))
    )
    (net (code "25") (name "Net-(EPD_C1-Pad1)") (class "Default")
      (node (ref "EPD_C1") (pin "1") (pinfunction "1_1") (pintype "passive"))
      (node (ref "J1") (pin "4") (pinfunction "4_4") (pintype "bidirectional"))
    )
    (net (code "26") (name "Net-(EPD_C2-Pad1)") (class "Default")
      (node (ref "EPD_C2") (pin "1") (pinfunction "1_1") (pintype "passive"))
      (node (ref "J1") (pin "5") (pinfunction "5_5") (pintype "bidirectional"))
    )
    (net (code "27") (name "Net-(EPD_C5-Pad1)") (class "Default")
      (node (ref "EPD_C5") (pin "1") (pinfunction "1_1") (pintype "passive"))
      (node (ref "J1") (pin "15") (pinfunction "15_15") (pintype "bidirectional"))
    )
    (net (code "28") (name "Net-(EPD_C6-Pad1)") (class "Default")
      (node (ref "EPD_C6") (pin "1") (pinfunction "1_1") (pintype "passive"))
      (node (ref "J1") (pin "18") (pinfunction "18_18") (pintype "bidirectional"))
    )
    (net (code "29") (name "Net-(EPD_C7-Pad1)") (class "Default")
      (node (ref "EPD_C7") (pin "1") (pinfunction "1_1") (pintype "passive"))
      (node (ref "J1") (pin "19") (pinfunction "19_19") (pintype "bidirectional"))
    )
    (net (code "30") (name "Net-(EPD_C8-Pad1)") (class "Default")
      (node (ref "EPD_C8") (pin "1") (pinfunction "1_1") (pintype "passive"))
      (node (ref "J1") (pin "20") (pinfunction "20_20") (pintype "bidirectional"))
    )
    (net (code "31") (name "Net-(EPD_C10-Pad1)") (class "Default")
      (node (ref "EPD_C10") (pin "1") (pinfunction "1_1") (pintype "passive"))
      (node (ref "J1") (pin "22") (pinfunction "22_22") (pintype "bidirectional"))
    )
    (net (code "32") (name "Net-(EPD_C12-Pad1)") (class "Default")
      (node (ref "EPD_C12") (pin "1") (pinfunction "1_1") (pintype "passive"))
      (node (ref "J1") (pin "24") (pinfunction "24_24") (pintype "bidirectional"))
    )
    (net (code "33") (name "Net-(IC1-CT)") (class "Default")
      (node (ref "C_DELAY") (pin "1") (pinfunction "1_1") (pintype "passive"))
      (node (ref "IC1") (pin "5") (pinfunction "CT_5") (pintype "bidirectional"))
    )
    (net (code "34") (name "Net-(J2-PadA5)") (class "Default")
      (node (ref "J2") (pin "A5") (pinfunction "A5_A5") (pintype "bidirectional"))
      (node (ref "R2-USB1") (pin "2") (pinfunction "2_2") (pintype "passive"))
    )
    (net (code "35") (name "Net-(J2-PadB5)") (class "Default")
      (node (ref "J2") (pin "B5") (pinfunction "B5_B5") (pintype "bidirectional"))
      (node (ref "R2-USB") (pin "1") (pinfunction "1_1") (pintype "passive"))
    )
    (net (code "36") (name "Net-(MCP73831-PROG)") (class "Default")
      (node (ref "MCP73831") (pin "5") (pinfunction "PROG_5") (pintype "input"))
      (node (ref "R2_BAT") (pin "2") (pinfunction "2_2") (pintype "passive"))
    )
    (net (code "37") (name "Net-(MCP73831-STAT)") (class "Default")
      (node (ref "MCP73831") (pin "1") (pinfunction "STAT_1") (pintype "output"))
      (node (ref "R1_BAT") (pin "1") (pinfunction "1_1") (pintype "passive"))
    )
    (net (code "38") (name "PREVGH") (class "Default")
      (node (ref "D5") (pin "2") (pinfunction "A_2") (pintype "bidirectional"))
      (node (ref "EPD_C9") (pin "1") (pinfunction "1_1") (pintype "passive"))
      (node (ref "J1") (pin "21") (pinfunction "21_21") (pintype "bidirectional"))
    )
    (net (code "39") (name "PREVGL") (class "Default")
      (node (ref "D4") (pin "2") (pinfunction "A_2") (pintype "bidirectional"))
      (node (ref "EPD_C11") (pin "1") (pinfunction "1_1") (pintype "passive"))
      (node (ref "J1") (pin "23") (pinfunction "23_23") (pintype "bidirectional"))
    )
    (net (code "40") (name "RESE") (class "Default")
      (node (ref "J1") (pin "3") (pinfunction "3_3") (pintype "bidirectional"))
      (node (ref "Q3") (pin "2") (pinfunction "S_2") (pintype "bidirectional"))
      (node (ref "R3") (pin "2") (pinfunction "2_2") (pintype "passive"))
    )
    (net (code "41") (name "RESE'") (class "Default")
      (node (ref "R2") (pin "2") (pinfunction "2_2") (pintype "passive"))
      (node (ref "R3") (pin "1") (pinfunction "1_1") (pintype "passive"))
      (node (ref "SJ1") (pin "2") (pinfunction "2_2") (pintype "passive"))
    )
    (net (code "42") (name "RESET") (class "Default")
      (node (ref "C5") (pin "1") (pinfunction "1_1") (pintype "passive"))
      (node (ref "IC1") (pin "1") (pinfunction "VOUT_1") (pintype "bidirectional"))
      (node (ref "RESET_BUTTON") (pin "3") (pinfunction "3_3") (pintype "passive"))
      (node (ref "RESET_BUTTON") (pin "4") (pinfunction "4_4") (pintype "passive"))
      (node (ref "R_RESET") (pin "1") (pinfunction "1_1") (pintype "passive"))
      (node (ref "U2") (pin "3") (pinfunction "EN_3") (pintype "input"))
    )
    (net (code "43") (name "RTC_RST") (class "Default")
      (node (ref "U2") (pin "16") (pinfunction "IO18_16") (pintype "bidirectional"))
      (node (ref "U3") (pin "4") (pinfunction "~{RST}_4") (pintype "input"))
    )
    (net (code "44") (name "RX") (class "Default")
      (node (ref "TP2") (pin "TP") (pinfunction "TP_TP") (pintype "input"))
      (node (ref "U2") (pin "24") (pinfunction "RXD0/GPIO17_24") (pintype "bidirectional"))
    )
    (net (code "45") (name "SCK") (class "Default")
      (node (ref "D10") (pin "2") (pinfunction "2_2") (pintype "passive"))
      (node (ref "J1") (pin "13") (pinfunction "13_13") (pintype "bidirectional"))
      (node (ref "J4") (pin "P5") (pinfunction "CLK_P5") (pintype "bidirectional"))
      (node (ref "R6") (pin "1") (pinfunction "1_1") (pintype "passive"))
      (node (ref "TP8") (pin "TP") (pinfunction "TP_TP") (pintype "input"))
      (node (ref "U1") (pin "6") (pinfunction "CLK_6") (pintype "input"))
      (node (ref "U2") (pin "6") (pinfunction "IO6_6") (pintype "bidirectional"))
    )
    (net (code "46") (name "SCL") (class "Default")
      (node (ref "J3") (pin "1") (pinfunction "1_1") (pintype "power_in"))
      (node (ref "R2-PINH") (pin "1") (pinfunction "1_1") (pintype "passive"))
      (node (ref "SENSOR2") (pin "4") (pinfunction "SCK_4") (pintype "input"))
      (node (ref "U2") (pin "20") (pinfunction "IO22_20") (pintype "bidirectional"))
      (node (ref "U3") (pin "16") (pinfunction "SCL_16") (pintype "input"))
      (node (ref "U4") (pin "7") (pinfunction "SCL_7") (pintype "input"))
    )
    (net (code "47") (name "SDA") (class "Default")
      (node (ref "J3") (pin "2") (pinfunction "2_2") (pintype "power_in"))
      (node (ref "R1-PINH") (pin "1") (pinfunction "1_1") (pintype "passive"))
      (node (ref "SENSOR2") (pin "3") (pinfunction "SDI_3") (pintype "bidirectional"))
      (node (ref "U2") (pin "19") (pinfunction "IO21_19") (pintype "bidirectional"))
      (node (ref "U3") (pin "15") (pinfunction "SDA_15") (pintype "bidirectional"))
      (node (ref "U4") (pin "8") (pinfunction "SDA_8") (pintype "bidirectional"))
    )
    (net (code "48") (name "SRC") (class "Default")
      (node (ref "C4") (pin "2") (pinfunction "2_2") (pintype "passive"))
      (node (ref "D5") (pin "1") (pinfunction "K_1") (pintype "bidirectional"))
      (node (ref "L1") (pin "1") (pinfunction "1_1") (pintype "passive"))
      (node (ref "Q3") (pin "3") (pinfunction "D_3") (pintype "bidirectional"))
    )
    (net (code "49") (name "SS_SD") (class "Default")
      (node (ref "D8") (pin "2") (pinfunction "2_2") (pintype "passive"))
      (node (ref "J4") (pin "P2") (pinfunction "CD/DAT3_P2") (pintype "bidirectional"))
      (node (ref "R10") (pin "1") (pinfunction "1_1") (pintype "passive"))
      (node (ref "U2") (pin "4") (pinfunction "IO4_4") (pintype "bidirectional"))
    )
    (net (code "50") (name "TX") (class "Default")
      (node (ref "TP1") (pin "TP") (pinfunction "TP_TP") (pintype "input"))
      (node (ref "U2") (pin "25") (pinfunction "TXD0/GPIO16_25") (pintype "bidirectional"))
    )
    (net (code "51") (name "USB_D+") (class "Default")
      (node (ref "D1") (pin "4") (pinfunction "I/O2_2_4") (pintype "bidirectional"))
      (node (ref "U2") (pin "14") (pinfunction "IO13_14") (pintype "bidirectional"))
    )
    (net (code "52") (name "USB_D-") (class "Default")
      (node (ref "D1") (pin "6") (pinfunction "I/O1_2_6") (pintype "bidirectional"))
      (node (ref "U2") (pin "13") (pinfunction "IO12_13") (pintype "bidirectional"))
    )
    (net (code "53") (name "VBAT") (class "Default")
      (node (ref "C2_BAT") (pin "1") (pinfunction "1_1") (pintype "passive"))
      (node (ref "MCP73831") (pin "3") (pinfunction "VBAT_3") (pintype "power_in"))
      (node (ref "Q1") (pin "3") (pinfunction "D_3") (pintype "bidirectional"))
      (node (ref "TP3") (pin "TP") (pinfunction "TP_TP") (pintype "input"))
      (node (ref "U4") (pin "2") (pinfunction "CELL_2") (pintype "power_in"))
      (node (ref "U4") (pin "3") (pinfunction "VDD_3") (pintype "power_in"))
    )
    (net (code "54") (name "VBUS") (class "Default")
      (node (ref "C1_BAT") (pin "1") (pinfunction "1_1") (pintype "passive"))
      (node (ref "C4_USB") (pin "1") (pinfunction "1_1") (pintype "passive"))
      (node (ref "C5_USB") (pin "1") (pinfunction "1_1") (pintype "passive"))
      (node (ref "CHG_LED") (pin "A") (pinfunction "A_A") (pintype "passive"))
      (node (ref "D1") (pin "2") (pinfunction "GND_2") (pintype "bidirectional"))
      (node (ref "D2") (pin "2") (pinfunction "ANODE_2") (pintype "bidirectional"))
      (node (ref "MCP73831") (pin "4") (pinfunction "VIN_4") (pintype "power_in"))
      (node (ref "PFMF.050.1") (pin "2") (pinfunction "2_2") (pintype "passive"))
      (node (ref "Q1") (pin "1") (pinfunction "G_1") (pintype "bidirectional"))
      (node (ref "R1_PWRUSB") (pin "2") (pinfunction "2_2") (pintype "passive"))
      (node (ref "TP14") (pin "TP") (pinfunction "TP_TP") (pintype "input"))
    )
    (net (code "55") (name "VRTC") (class "Default")
      (node (ref "C10_SUPERCAP") (pin "2") (pinfunction "2_2") (pintype "passive"))
      (node (ref "C8") (pin "1") (pinfunction "1_1") (pintype "passive"))
      (node (ref "R_CAPACITOR") (pin "2") (pinfunction "2_2") (pintype "passive"))
      (node (ref "U3") (pin "14") (pinfunction "VBAT_14") (pintype "power_in"))
    )
    (net (code "56") (name "VUSB") (class "Default")
      (node (ref "J2") (pin "A4") (pinfunction "A4_A4") (pintype "bidirectional"))
      (node (ref "J2") (pin "A9") (pinfunction "A9_A9") (pintype "bidirectional"))
      (node (ref "J2") (pin "B4") (pinfunction "B4_B4") (pintype "bidirectional"))
      (node (ref "J2") (pin "B9") (pinfunction "B9_B9") (pintype "bidirectional"))
      (node (ref "PFMF.050.1") (pin "1") (pinfunction "1_1") (pintype "passive"))
    )
    (net (code "57") (name "unconnected-(IC1-NC-Pad4)") (class "Default")
      (node (ref "IC1") (pin "4") (pinfunction "NC_4") (pintype "no_connect"))
    )
    (net (code "58") (name "unconnected-(IC4-NC-Pad4)") (class "Default")
      (node (ref "IC4") (pin "4") (pinfunction "NC_4") (pintype "no_connect"))
    )
    (net (code "59") (name "unconnected-(J1-Pad1)") (class "Default")
      (node (ref "J1") (pin "1") (pinfunction "1_1") (pintype "bidirectional"))
    )
    (net (code "60") (name "unconnected-(J1-Pad6)") (class "Default")
      (node (ref "J1") (pin "6") (pinfunction "6_6") (pintype "bidirectional"))
    )
    (net (code "61") (name "unconnected-(J1-Pad7)") (class "Default")
      (node (ref "J1") (pin "7") (pinfunction "7_7") (pintype "bidirectional"))
    )
    (net (code "62") (name "unconnected-(J2-PadA8)") (class "Default")
      (node (ref "J2") (pin "A8") (pinfunction "A8_A8") (pintype "bidirectional"))
    )
    (net (code "63") (name "unconnected-(J2-PadB8)") (class "Default")
      (node (ref "J2") (pin "B8") (pinfunction "B8_B8") (pintype "bidirectional"))
    )
    (net (code "64") (name "unconnected-(J4-DAT1-PadP8)") (class "Default")
      (node (ref "J4") (pin "P8") (pinfunction "DAT1_P8") (pintype "bidirectional"))
    )
    (net (code "65") (name "unconnected-(J4-DAT2-PadP1)") (class "Default")
      (node (ref "J4") (pin "P1") (pinfunction "DAT2_P1") (pintype "bidirectional"))
    )
    (net (code "66") (name "unconnected-(J4-DETECTION_1-PadS1)") (class "Default")
      (node (ref "J4") (pin "S1") (pinfunction "DETECTION_1_S1") (pintype "bidirectional"))
    )
    (net (code "67") (name "unconnected-(J4-DETECTION_2-PadS2)") (class "Default")
      (node (ref "J4") (pin "S2") (pinfunction "DETECTION_2_S2") (pintype "bidirectional"))
    )
    (net (code "68") (name "unconnected-(U2-NC-Pad22)") (class "Default")
      (node (ref "U2") (pin "22") (pinfunction "NC_22") (pintype "no_connect"))
    )
    (net (code "69") (name "unconnected-(U4-~{ALERT}-Pad5)") (class "Default")
      (node (ref "U4") (pin "5") (pinfunction "~{ALERT}_5") (pintype "output"))
    )
  )
)
